# Regulator12V.net
KiCad netlist of a schematic drawn in Altium Designer
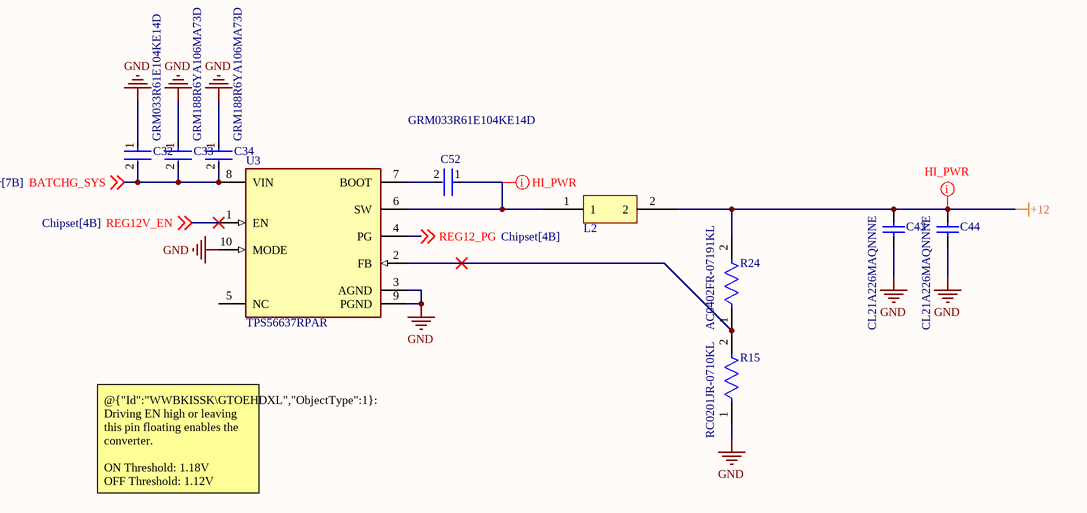
[diagram p0: Regulator12V.SchDoc]

(export (version "E")
  (design (tool "Eeschema 10.0.6"))
  (components
    (comp (ref "C32")
      (value "GRM033R61E104KE14D")
      (footprint "FP-GRM033-0_03-IPC_B")
      (description "Chip Multilayer Ceramic Capacitors for General Purpose, 0201, 0.10uF, X5R, 15%, 10%, 25V")
      (fields (field (name "TOLERANCE") "10%"))
      (libsource (lib "Altium Content Vault") (part "b4654b650e69147ec39a6b967a45e02"))
    )
    (comp (ref "C33")
      (value "GRM188R6YA106MA73D")
      (footprint "FP-GRM188-0_2-IPC_C")
      (description "Chip Multilayer Ceramic Capacitors for General Purpose, 0603, 10uF, X5R, 15%, 20%, 35V")
      (fields (field (name "TOLERANCE") "20%"))
      (libsource (lib "Altium Content Vault") (part "11868f565c42a9108669ba33697ecf6"))
    )
    (comp (ref "C34")
      (value "GRM188R6YA106MA73D")
      (footprint "FP-GRM188-0_2-IPC_C")
      (description "Chip Multilayer Ceramic Capacitors for General Purpose, 0603, 10uF, X5R, 15%, 20%, 35V")
      (fields (field (name "TOLERANCE") "20%"))
      (libsource (lib "Altium Content Vault") (part "11868f565c42a9108669ba33697ecf6"))
    )
    (comp (ref "C43")
      (value "CL21A226MAQNNNE")
      (footprint "CAPC2013X140X45LL15T25")
      (description "Multi-layer Ceramic Capacitor, 22 uF, -55 to 85 degC, 2-Pin SMD (0805), RoHS, Tape and Reel")
      (fields (field (name "MANUFACTURER") "Samsung Electro-Mechanics") (field (name "TOLERANCE") "±20%"))
      (libsource (lib "Altium Content Vault") (part "CAP-NP-2"))
    )
    (comp (ref "C44")
      (value "CL21A226MAQNNNE")
      (footprint "CAPC2013X140X45LL15T25")
      (description "Multi-layer Ceramic Capacitor, 22 uF, -55 to 85 degC, 2-Pin SMD (0805), RoHS, Tape and Reel")
      (fields (field (name "MANUFACTURER") "Samsung Electro-Mechanics") (field (name "TOLERANCE") "±20%"))
      (libsource (lib "Altium Content Vault") (part "CAP-NP-2"))
    )
    (comp (ref "C52")
      (value "GRM033R61E104KE14D")
      (footprint "FP-GRM033-0_03-IPC_B")
      (description "Chip Multilayer Ceramic Capacitors for General Purpose, 0201, 0.10uF, X5R, 15%, 10%, 25V")
      (fields (field (name "TOLERANCE") "10%"))
      (libsource (lib "Altium Content Vault") (part "b4654b650e69147ec39a6b967a45e02"))
    )
    (comp (ref "L2")
      (value "IHLP3232DZER5R6M11")
      (footprint "IHLP3232DZER5R6M11")
      (libsource (lib "IHLP3232DZER5R6M11") (part "IHLP3232DZER5R6M11"))
    )
    (comp (ref "R15")
      (value "RC0201JR-0710KL")
      (footprint "FP-RC0201-0_26-IPC_C")
      (description "RES SMD 10K OHM 5% 1/20W 0201")
      (fields (field (name "TOLERANCE") "5%"))
      (libsource (lib "Altium Content Vault") (part "1029c3af85768c4190bb7ad29bc67b5"))
    )
    (comp (ref "R24")
      (value "AC0402FR-07191KL")
      (footprint "FP-AC0402-IPC_C")
      (description "RES 191kΩ ±1% 0.063W 0402")
      (fields (field (name "TOLERANCE") "1%"))
      (libsource (lib "Altium Content Vault") (part "1029c3af85768c4190bb7ad29bc67b5"))
    )
    (comp (ref "U3")
      (value "TPS56637RPAR")
      (footprint "FP-RPA0010A-MFG")
      (description "IC POWER MANAGEMENT")
      (fields
        (field (name "OCTOPART") "https://octopart.com/tps56637rpar-texas+instruments-97650653")
        (field (name "MANUFACTURER") "Texas Instruments")
      )
      (libsource (lib "Altium Content Vault") (part "31007e10bcfaaa9b7385bfd54c3e755"))
    )
  )
  (nets
    (net (code "1") (name "+12") (class "Default")
      (node (ref "C43") (pin "2") (pinfunction "2_2") (pintype "passive"))
      (node (ref "C44") (pin "2") (pinfunction "2_2") (pintype "passive"))
      (node (ref "L2") (pin "2") (pinfunction "2_2") (pintype "passive"))
      (node (ref "R24") (pin "2") (pinfunction "2_2") (pintype "passive"))
    )
    (net (code "2") (name "BATCHG_SYS") (class "Default")
      (node (ref "C32") (pin "2") (pinfunction "2_2") (pintype "passive"))
      (node (ref "C33") (pin "2") (pinfunction "2_2") (pintype "passive"))
      (node (ref "C34") (pin "2") (pinfunction "2_2") (pintype "passive"))
      (node (ref "U3") (pin "8") (pinfunction "VIN_8") (pintype "power_in"))
    )
    (net (code "3") (name "GND") (class "Default")
      (node (ref "C32") (pin "1") (pinfunction "1_1") (pintype "passive"))
      (node (ref "C33") (pin "1") (pinfunction "1_1") (pintype "passive"))
      (node (ref "C34") (pin "1") (pinfunction "1_1") (pintype "passive"))
      (node (ref "C43") (pin "1") (pinfunction "1_1") (pintype "passive"))
      (node (ref "C44") (pin "1") (pinfunction "1_1") (pintype "passive"))
      (node (ref "R15") (pin "1") (pinfunction "1_1") (pintype "passive"))
      (node (ref "U3") (pin "10") (pinfunction "MODE_10") (pintype "input"))
      (node (ref "U3") (pin "3") (pinfunction "AGND_3") (pintype "power_in"))
      (node (ref "U3") (pin "9") (pinfunction "PGND_9") (pintype "power_in"))
    )
    (net (code "4") (name "Net-(U3-BOOT)") (class "Default")
      (node (ref "C52") (pin "2") (pinfunction "2_2") (pintype "passive"))
      (node (ref "U3") (pin "7") (pinfunction "BOOT_7") (pintype "power_in"))
    )
    (net (code "5") (name "Net-(U3-FB)") (class "Default")
      (node (ref "R15") (pin "2") (pinfunction "2_2") (pintype "passive"))
      (node (ref "R24") (pin "1") (pinfunction "1_1") (pintype "passive"))
      (node (ref "U3") (pin "2") (pinfunction "FB_2") (pintype "input"))
    )
    (net (code "6") (name "Net-(U3-SW)") (class "Default")
      (node (ref "C52") (pin "1") (pinfunction "1_1") (pintype "passive"))
      (node (ref "L2") (pin "1") (pinfunction "1_1") (pintype "passive"))
      (node (ref "U3") (pin "6") (pinfunction "SW_6") (pintype "power_in"))
    )
    (net (code "7") (name "REG12V_EN") (class "Default")
      (node (ref "U3") (pin "1") (pinfunction "EN_1") (pintype "input"))
    )
    (net (code "8") (name "REG12_PG") (class "Default")
      (node (ref "U3") (pin "4") (pinfunction "PG_4") (pintype "open_collector"))
    )
    (net (code "9") (name "unconnected-(U3-NC-Pad5)") (class "Default")
      (node (ref "U3") (pin "5") (pinfunction "NC_5") (pintype "passive"))
    )
  )
)
